# Programadapter.net
KiCad netlist of a schematic drawn in Altium Designer
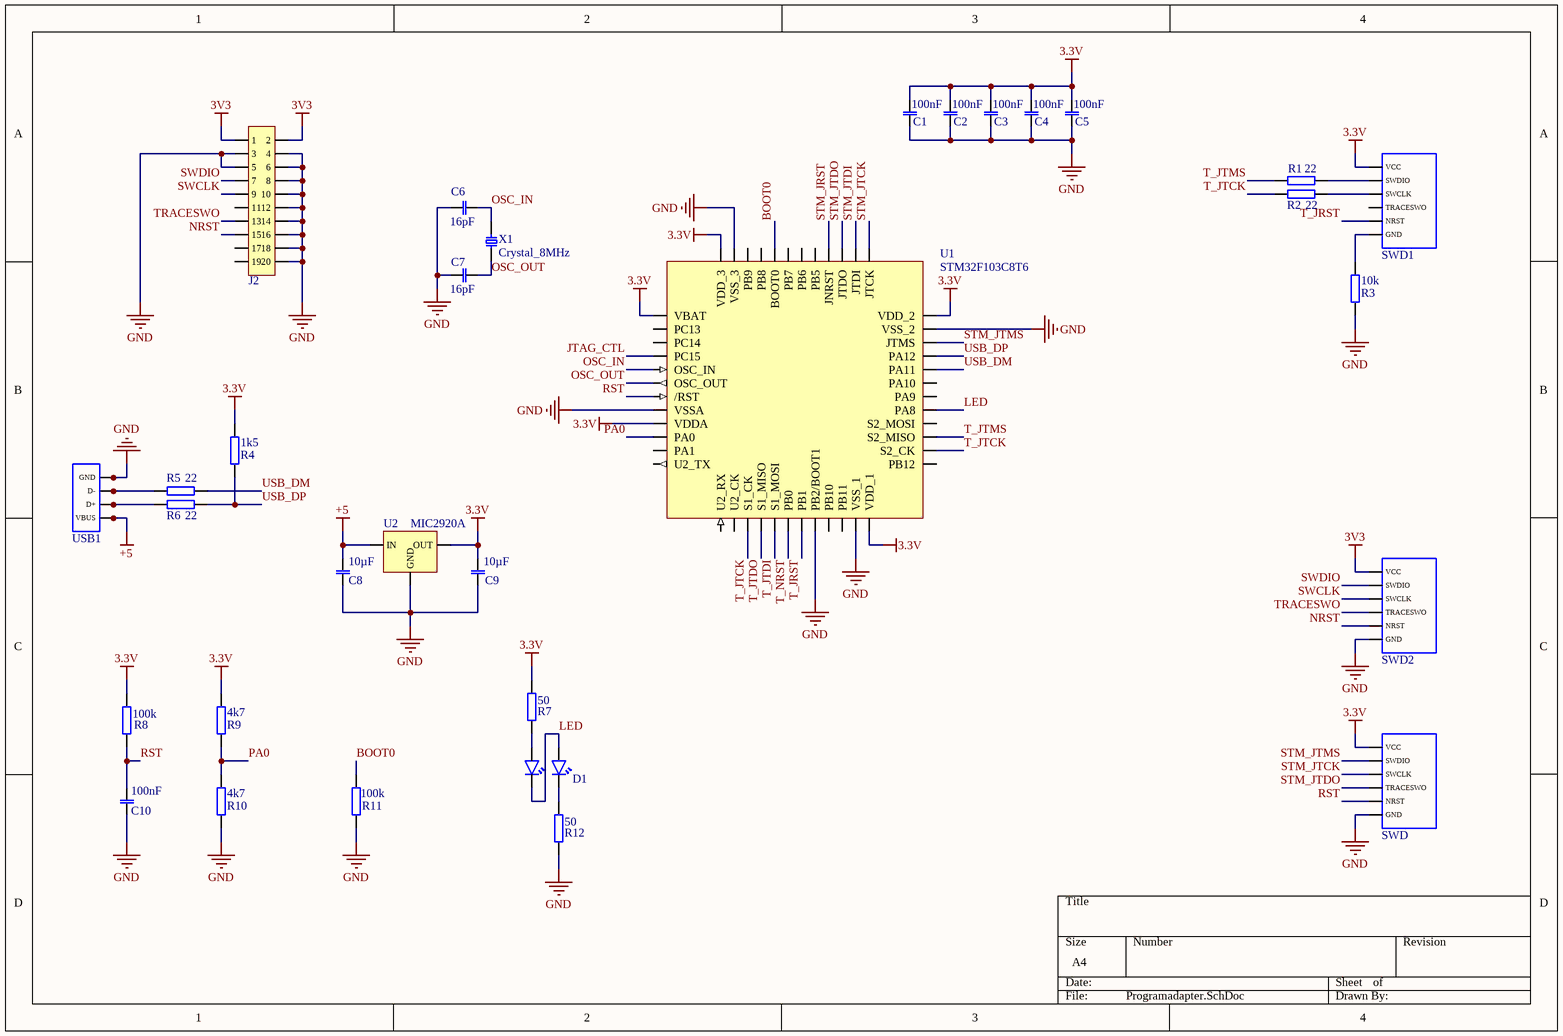
[diagram p0: Programadapter.SchDoc]

(export (version "E")
  (design (tool "Eeschema 10.0.6"))
  (components
    (comp (ref "C1")
      (value "Capacitor_0603")
      (footprint "C_0603_Chip2PinSM127P600-8N")
      (fields (field (name "CAPACITY") "100nF"))
      (libsource (lib "MiniWS") (part "Capacitor_0603"))
    )
    (comp (ref "C2")
      (value "Capacitor_0603")
      (footprint "C_0603_Chip2PinSM127P600-8N")
      (fields (field (name "CAPACITY") "100nF"))
      (libsource (lib "MiniWS") (part "Capacitor_0603"))
    )
    (comp (ref "C3")
      (value "Capacitor_0603")
      (footprint "C_0603_Chip2PinSM127P600-8N")
      (fields (field (name "CAPACITY") "100nF"))
      (libsource (lib "MiniWS") (part "Capacitor_0603"))
    )
    (comp (ref "C4")
      (value "Capacitor_0603")
      (footprint "C_0603_Chip2PinSM127P600-8N")
      (fields (field (name "CAPACITY") "100nF"))
      (libsource (lib "MiniWS") (part "Capacitor_0603"))
    )
    (comp (ref "C5")
      (value "Capacitor_0603")
      (footprint "C_0603_Chip2PinSM127P600-8N")
      (fields (field (name "CAPACITY") "100nF"))
      (libsource (lib "MiniWS") (part "Capacitor_0603"))
    )
    (comp (ref "C6")
      (value "Capacitor_0603")
      (footprint "C_0603_Chip2PinSM127P600-8N")
      (fields (field (name "CAPACITY") "16pF"))
      (libsource (lib "MiniWS") (part "Capacitor_0603"))
    )
    (comp (ref "C7")
      (value "Capacitor_0603")
      (footprint "C_0603_Chip2PinSM127P600-8N")
      (fields (field (name "CAPACITY") "16pF"))
      (libsource (lib "MiniWS") (part "Capacitor_0603"))
    )
    (comp (ref "C8")
      (value "Capacitor_0805")
      (footprint "10uF_0805_Chip2PinSM127P600-8N")
      (fields (field (name "CAPACITY") "10µF"))
      (libsource (lib "MiniWS") (part "Capacitor_0805"))
    )
    (comp (ref "C9")
      (value "Capacitor_0805")
      (footprint "10uF_0805_Chip2PinSM127P600-8N")
      (fields (field (name "CAPACITY") "10µF"))
      (libsource (lib "MiniWS") (part "Capacitor_0805"))
    )
    (comp (ref "C10")
      (value "Capacitor_0603")
      (footprint "C_0603_Chip2PinSM127P600-8N")
      (fields (field (name "CAPACITY") "100nF"))
      (libsource (lib "MiniWS") (part "Capacitor_0603"))
    )
    (comp (ref "D1")
      (value "LTST_LED_RED_GREEN")
      (footprint "LTST_LED_GREEN_RED")
      (libsource (lib "MiniWS") (part "LTST_LED_RED_GREEN"))
    )
    (comp (ref "J2")
      (value "JTAG_Header")
      (footprint "JTAG_Header")
      (libsource (lib "MiniWS") (part "JTAG_Header"))
    )
    (comp (ref "R1")
      (value "Resistor_0603")
      (footprint "R_0603_Chip2PinSM127P600-8N")
      (fields (field (name "RESISTANCE") "22"))
      (libsource (lib "MiniWS") (part "Resistor_0603"))
    )
    (comp (ref "R2")
      (value "Resistor_0603")
      (footprint "R_0603_Chip2PinSM127P600-8N")
      (fields (field (name "RESISTANCE") "22"))
      (libsource (lib "MiniWS") (part "Resistor_0603"))
    )
    (comp (ref "R3")
      (value "Resistor_0603")
      (footprint "R_0603_Chip2PinSM127P600-8N")
      (fields (field (name "RESISTANCE") "10k"))
      (libsource (lib "MiniWS") (part "Resistor_0603"))
    )
    (comp (ref "R4")
      (value "Resistor_0603")
      (footprint "R_0603_Chip2PinSM127P600-8N")
      (fields (field (name "RESISTANCE") "1k5"))
      (libsource (lib "MiniWS") (part "Resistor_0603"))
    )
    (comp (ref "R5")
      (value "Resistor_0603")
      (footprint "R_0603_Chip2PinSM127P600-8N")
      (fields (field (name "RESISTANCE") "22"))
      (libsource (lib "MiniWS") (part "Resistor_0603"))
    )
    (comp (ref "R6")
      (value "Resistor_0603")
      (footprint "R_0603_Chip2PinSM127P600-8N")
      (fields (field (name "RESISTANCE") "22"))
      (libsource (lib "MiniWS") (part "Resistor_0603"))
    )
    (comp (ref "R7")
      (value "Resistor_0603")
      (footprint "R_0603_Chip2PinSM127P600-8N")
      (fields (field (name "RESISTANCE") "50"))
      (libsource (lib "MiniWS") (part "Resistor_0603"))
    )
    (comp (ref "R8")
      (value "Resistor_0603")
      (footprint "R_0603_Chip2PinSM127P600-8N")
      (fields (field (name "RESISTANCE") "100k"))
      (libsource (lib "MiniWS") (part "Resistor_0603"))
    )
    (comp (ref "R9")
      (value "Resistor_0603")
      (footprint "R_0603_Chip2PinSM127P600-8N")
      (fields (field (name "RESISTANCE") "4k7"))
      (libsource (lib "MiniWS") (part "Resistor_0603"))
    )
    (comp (ref "R10")
      (value "Resistor_0603")
      (footprint "R_0603_Chip2PinSM127P600-8N")
      (fields (field (name "RESISTANCE") "4k7"))
      (libsource (lib "MiniWS") (part "Resistor_0603"))
    )
    (comp (ref "R11")
      (value "Resistor_0603")
      (footprint "R_0603_Chip2PinSM127P600-8N")
      (fields (field (name "RESISTANCE") "100k"))
      (libsource (lib "MiniWS") (part "Resistor_0603"))
    )
    (comp (ref "R12")
      (value "Resistor_0603")
      (footprint "R_0603_Chip2PinSM127P600-8N")
      (fields (field (name "RESISTANCE") "50"))
      (libsource (lib "MiniWS") (part "Resistor_0603"))
    )
    (comp (ref "SWD")
      (value "ProgrammingHeader")
      (footprint "ProgrammingHeader")
      (libsource (lib "MiniWS") (part "ProgrammingHeader"))
    )
    (comp (ref "SWD1")
      (value "ProgrammingHeader")
      (footprint "ProgrammingHeader")
      (libsource (lib "MiniWS") (part "ProgrammingHeader"))
    )
    (comp (ref "SWD2")
      (value "ProgrammingHeader")
      (footprint "ProgrammingHeader")
      (libsource (lib "MiniWS") (part "ProgrammingHeader"))
    )
    (comp (ref "U1")
      (value "STM32F103C8T6")
      (footprint "STM32F103CBT_LQFP48")
      (libsource (lib "MiniWS") (part "STM32F103C8T6"))
    )
    (comp (ref "U2")
      (value "MIC2920A")
      (footprint "MIC2920A_SOT230P710X170-4N")
      (libsource (lib "MiniWS") (part "MIC2920_3V3_VoltageReg"))
    )
    (comp (ref "USB1")
      (value "USB-C_simplified")
      (footprint "USB-C_receptacle")
      (description "USB Type C receptacle simplified with just data and supply pins")
      (libsource (lib "MiniWS") (part "USB-C_simplified"))
    )
    (comp (ref "X1")
      (value "Crystal_8MHz")
      (footprint "Crystal_8MHz")
      (description "8MHz Crystall SMD")
      (libsource (lib "MiniWS") (part "Crystal_8MHz"))
    )
  )
  (nets
    (net (code "1") (name "+5") (class "Default")
      (node (ref "C8") (pin "1") (pinfunction "1_1") (pintype "passive"))
      (node (ref "U2") (pin "1") (pinfunction "IN_1") (pintype "passive"))
      (node (ref "USB1") (pin "A4") (pinfunction "VBUS_A4") (pintype "passive"))
      (node (ref "USB1") (pin "A9") (pinfunction "VBUS_A9") (pintype "passive"))
      (node (ref "USB1") (pin "B4") (pinfunction "VBUS_B4") (pintype "passive"))
      (node (ref "USB1") (pin "B9") (pinfunction "VBUS_B9") (pintype "passive"))
    )
    (net (code "2") (name "/BOOT0") (class "Default")
      (node (ref "R11") (pin "2") (pinfunction "2_2") (pintype "passive"))
      (node (ref "U1") (pin "44") (pinfunction "BOOT0_44") (pintype "bidirectional"))
    )
    (net (code "3") (name "/JTAG_CTL") (class "Default")
      (node (ref "U1") (pin "4") (pinfunction "PC15_4") (pintype "bidirectional"))
    )
    (net (code "4") (name "/LED") (class "Default")
      (node (ref "D1") (pin "2") (pinfunction "2_2") (pintype "passive"))
      (node (ref "D1") (pin "4") (pinfunction "4_4") (pintype "passive"))
      (node (ref "U1") (pin "29") (pinfunction "PA8_29") (pintype "bidirectional"))
    )
    (net (code "5") (name "/NRST") (class "Default")
      (node (ref "J2") (pin "15") (pinfunction "15_15") (pintype "passive"))
      (node (ref "SWD2") (pin "5") (pinfunction "NRST_5") (pintype "passive"))
    )
    (net (code "6") (name "/OSC_IN") (class "Default")
      (node (ref "C6") (pin "2") (pinfunction "2_2") (pintype "passive"))
      (node (ref "U1") (pin "5") (pinfunction "OSC_IN_5") (pintype "input"))
      (node (ref "X1") (pin "2") (pinfunction "2_2") (pintype "passive"))
    )
    (net (code "7") (name "/OSC_OUT") (class "Default")
      (node (ref "C7") (pin "2") (pinfunction "2_2") (pintype "passive"))
      (node (ref "U1") (pin "6") (pinfunction "OSC_OUT_6") (pintype "output"))
      (node (ref "X1") (pin "1") (pinfunction "1_1") (pintype "passive"))
    )
    (net (code "8") (name "/PA0") (class "Default")
      (node (ref "R10") (pin "2") (pinfunction "2_2") (pintype "passive"))
      (node (ref "R9") (pin "1") (pinfunction "1_1") (pintype "passive"))
      (node (ref "U1") (pin "10") (pinfunction "PA0_10") (pintype "bidirectional"))
    )
    (net (code "9") (name "/RST") (class "Default")
      (node (ref "C10") (pin "1") (pinfunction "1_1") (pintype "passive"))
      (node (ref "R8") (pin "1") (pinfunction "1_1") (pintype "passive"))
      (node (ref "SWD") (pin "5") (pinfunction "NRST_5") (pintype "passive"))
      (node (ref "U1") (pin "7") (pinfunction "/RST_7") (pintype "input"))
    )
    (net (code "10") (name "/STM_JRST") (class "Default")
      (node (ref "U1") (pin "40") (pinfunction "JNRST_40") (pintype "bidirectional"))
    )
    (net (code "11") (name "/STM_JTCK") (class "Default")
      (node (ref "SWD") (pin "3") (pinfunction "SWCLK_3") (pintype "passive"))
      (node (ref "U1") (pin "37") (pinfunction "JTCK_37") (pintype "bidirectional"))
    )
    (net (code "12") (name "/STM_JTDI") (class "Default")
      (node (ref "U1") (pin "38") (pinfunction "JTDI_38") (pintype "bidirectional"))
    )
    (net (code "13") (name "/STM_JTDO") (class "Default")
      (node (ref "SWD") (pin "4") (pinfunction "TRACESWO_4") (pintype "passive"))
      (node (ref "U1") (pin "39") (pinfunction "JTDO_39") (pintype "bidirectional"))
    )
    (net (code "14") (name "/STM_JTMS") (class "Default")
      (node (ref "SWD") (pin "2") (pinfunction "SWDIO_2") (pintype "passive"))
      (node (ref "U1") (pin "34") (pinfunction "JTMS_34") (pintype "bidirectional"))
    )
    (net (code "15") (name "/SWCLK") (class "Default")
      (node (ref "J2") (pin "9") (pinfunction "9_9") (pintype "passive"))
      (node (ref "SWD2") (pin "3") (pinfunction "SWCLK_3") (pintype "passive"))
    )
    (net (code "16") (name "/SWDIO") (class "Default")
      (node (ref "J2") (pin "7") (pinfunction "7_7") (pintype "passive"))
      (node (ref "SWD2") (pin "2") (pinfunction "SWDIO_2") (pintype "passive"))
    )
    (net (code "17") (name "/TRACESWO") (class "Default")
      (node (ref "J2") (pin "13") (pinfunction "13_13") (pintype "passive"))
      (node (ref "SWD2") (pin "4") (pinfunction "TRACESWO_4") (pintype "passive"))
    )
    (net (code "18") (name "/T_JRST") (class "Default")
      (node (ref "SWD1") (pin "5") (pinfunction "NRST_5") (pintype "passive"))
      (node (ref "U1") (pin "19") (pinfunction "PB1_19") (pintype "passive"))
    )
    (net (code "19") (name "/T_JTCK") (class "Default")
      (node (ref "R2") (pin "1") (pinfunction "1_1") (pintype "passive"))
      (node (ref "U1") (pin "15") (pinfunction "S1_CK_15") (pintype "passive"))
      (node (ref "U1") (pin "26") (pinfunction "S2_CK_26") (pintype "passive"))
    )
    (net (code "20") (name "/T_JTDI") (class "Default")
      (node (ref "U1") (pin "17") (pinfunction "S1_MOSI_17") (pintype "passive"))
    )
    (net (code "21") (name "/T_JTDO") (class "Default")
      (node (ref "U1") (pin "16") (pinfunction "S1_MISO_16") (pintype "passive"))
    )
    (net (code "22") (name "/T_JTMS") (class "Default")
      (node (ref "R1") (pin "2") (pinfunction "2_2") (pintype "passive"))
      (node (ref "U1") (pin "27") (pinfunction "S2_MISO_27") (pintype "passive"))
    )
    (net (code "23") (name "/T_NRST") (class "Default")
      (node (ref "U1") (pin "18") (pinfunction "PB0_18") (pintype "passive"))
    )
    (net (code "24") (name "/USB_DM") (class "Default")
      (node (ref "R5") (pin "2") (pinfunction "2_2") (pintype "passive"))
      (node (ref "U1") (pin "32") (pinfunction "PA11_32") (pintype "bidirectional"))
    )
    (net (code "25") (name "/USB_DP") (class "Default")
      (node (ref "R4") (pin "1") (pinfunction "1_1") (pintype "passive"))
      (node (ref "R6") (pin "2") (pinfunction "2_2") (pintype "passive"))
      (node (ref "U1") (pin "33") (pinfunction "PA12_33") (pintype "bidirectional"))
    )
    (net (code "26") (name "3.3V") (class "Default")
      (node (ref "C1") (pin "1") (pinfunction "1_1") (pintype "passive"))
      (node (ref "C2") (pin "1") (pinfunction "1_1") (pintype "passive"))
      (node (ref "C3") (pin "1") (pinfunction "1_1") (pintype "passive"))
      (node (ref "C4") (pin "1") (pinfunction "1_1") (pintype "passive"))
      (node (ref "C5") (pin "1") (pinfunction "1_1") (pintype "passive"))
      (node (ref "C9") (pin "1") (pinfunction "1_1") (pintype "passive"))
      (node (ref "R4") (pin "2") (pinfunction "2_2") (pintype "passive"))
      (node (ref "R7") (pin "2") (pinfunction "2_2") (pintype "passive"))
      (node (ref "R8") (pin "2") (pinfunction "2_2") (pintype "passive"))
      (node (ref "R9") (pin "2") (pinfunction "2_2") (pintype "passive"))
      (node (ref "SWD") (pin "1") (pinfunction "VCC_1") (pintype "passive"))
      (node (ref "SWD1") (pin "1") (pinfunction "VCC_1") (pintype "passive"))
      (node (ref "U1") (pin "1") (pinfunction "VBAT_1") (pintype "passive"))
      (node (ref "U1") (pin "24") (pinfunction "VDD_1_24") (pintype "passive"))
      (node (ref "U1") (pin "36") (pinfunction "VDD_2_36") (pintype "passive"))
      (node (ref "U1") (pin "48") (pinfunction "VDD_3_48") (pintype "passive"))
      (node (ref "U1") (pin "9") (pinfunction "VDDA_9") (pintype "passive"))
      (node (ref "U2") (pin "3") (pinfunction "OUT_3") (pintype "passive"))
    )
    (net (code "27") (name "3V3") (class "Default")
      (node (ref "J2") (pin "1") (pinfunction "1_1") (pintype "passive"))
      (node (ref "J2") (pin "2") (pinfunction "2_2") (pintype "passive"))
      (node (ref "SWD2") (pin "1") (pinfunction "VCC_1") (pintype "passive"))
    )
    (net (code "28") (name "GND") (class "Default")
      (node (ref "C1") (pin "2") (pinfunction "2_2") (pintype "passive"))
      (node (ref "C10") (pin "2") (pinfunction "2_2") (pintype "passive"))
      (node (ref "C2") (pin "2") (pinfunction "2_2") (pintype "passive"))
      (node (ref "C3") (pin "2") (pinfunction "2_2") (pintype "passive"))
      (node (ref "C4") (pin "2") (pinfunction "2_2") (pintype "passive"))
      (node (ref "C5") (pin "2") (pinfunction "2_2") (pintype "passive"))
      (node (ref "C6") (pin "1") (pinfunction "1_1") (pintype "passive"))
      (node (ref "C7") (pin "1") (pinfunction "1_1") (pintype "passive"))
      (node (ref "C8") (pin "2") (pinfunction "2_2") (pintype "passive"))
      (node (ref "C9") (pin "2") (pinfunction "2_2") (pintype "passive"))
      (node (ref "J2") (pin "10") (pinfunction "10_10") (pintype "passive"))
      (node (ref "J2") (pin "12") (pinfunction "12_12") (pintype "passive"))
      (node (ref "J2") (pin "14") (pinfunction "14_14") (pintype "passive"))
      (node (ref "J2") (pin "16") (pinfunction "16_16") (pintype "passive"))
      (node (ref "J2") (pin "18") (pinfunction "18_18") (pintype "passive"))
      (node (ref "J2") (pin "20") (pinfunction "20_20") (pintype "passive"))
      (node (ref "J2") (pin "3") (pinfunction "3_3") (pintype "passive"))
      (node (ref "J2") (pin "4") (pinfunction "4_4") (pintype "passive"))
      (node (ref "J2") (pin "5") (pinfunction "5_5") (pintype "passive"))
      (node (ref "J2") (pin "6") (pinfunction "6_6") (pintype "passive"))
      (node (ref "J2") (pin "8") (pinfunction "8_8") (pintype "passive"))
      (node (ref "R10") (pin "1") (pinfunction "1_1") (pintype "passive"))
      (node (ref "R11") (pin "1") (pinfunction "1_1") (pintype "passive"))
      (node (ref "R12") (pin "1") (pinfunction "1_1") (pintype "passive"))
      (node (ref "R3") (pin "1") (pinfunction "1_1") (pintype "passive"))
      (node (ref "SWD") (pin "6") (pinfunction "GND_6") (pintype "passive"))
      (node (ref "SWD2") (pin "6") (pinfunction "GND_6") (pintype "passive"))
      (node (ref "U1") (pin "20") (pinfunction "PB2/BOOT1_20") (pintype "passive"))
      (node (ref "U1") (pin "23") (pinfunction "VSS_1_23") (pintype "passive"))
      (node (ref "U1") (pin "35") (pinfunction "VSS_2_35") (pintype "passive"))
      (node (ref "U1") (pin "47") (pinfunction "VSS_3_47") (pintype "passive"))
      (node (ref "U1") (pin "8") (pinfunction "VSSA_8") (pintype "passive"))
      (node (ref "U2") (pin "2") (pinfunction "GND_2") (pintype "passive"))
      (node (ref "USB1") (pin "A1") (pinfunction "GND_A1") (pintype "passive"))
      (node (ref "USB1") (pin "A12") (pinfunction "GND_A12") (pintype "passive"))
      (node (ref "USB1") (pin "B1") (pinfunction "GND_B1") (pintype "passive"))
      (node (ref "USB1") (pin "B12") (pinfunction "GND_B12") (pintype "passive"))
    )
    (net (code "29") (name "Net-(D1-Pad1)") (class "Default")
      (node (ref "D1") (pin "1") (pinfunction "1_1") (pintype "passive"))
      (node (ref "R7") (pin "1") (pinfunction "1_1") (pintype "passive"))
    )
    (net (code "30") (name "Net-(D1-Pad3)") (class "Default")
      (node (ref "D1") (pin "3") (pinfunction "3_3") (pintype "passive"))
      (node (ref "R12") (pin "2") (pinfunction "2_2") (pintype "passive"))
    )
    (net (code "31") (name "Net-(R5-Pad1)") (class "Default")
      (node (ref "R5") (pin "1") (pinfunction "1_1") (pintype "passive"))
      (node (ref "USB1") (pin "A7") (pinfunction "D-_A7") (pintype "passive"))
      (node (ref "USB1") (pin "B7") (pinfunction "D-_B7") (pintype "passive"))
    )
    (net (code "32") (name "Net-(R6-Pad1)") (class "Default")
      (node (ref "R6") (pin "1") (pinfunction "1_1") (pintype "passive"))
      (node (ref "USB1") (pin "A6") (pinfunction "D+_A6") (pintype "passive"))
      (node (ref "USB1") (pin "B6") (pinfunction "D+_B6") (pintype "passive"))
    )
    (net (code "33") (name "Net-(SWD1-GND)") (class "Default")
      (node (ref "R3") (pin "2") (pinfunction "2_2") (pintype "passive"))
      (node (ref "SWD1") (pin "6") (pinfunction "GND_6") (pintype "passive"))
    )
    (net (code "34") (name "Net-(SWD1-SWCLK)") (class "Default")
      (node (ref "R2") (pin "2") (pinfunction "2_2") (pintype "passive"))
      (node (ref "SWD1") (pin "3") (pinfunction "SWCLK_3") (pintype "passive"))
    )
    (net (code "35") (name "Net-(SWD1-SWDIO)") (class "Default")
      (node (ref "R1") (pin "1") (pinfunction "1_1") (pintype "passive"))
      (node (ref "SWD1") (pin "2") (pinfunction "SWDIO_2") (pintype "passive"))
    )
    (net (code "36") (name "unconnected-(J2-Pad11)") (class "Default")
      (node (ref "J2") (pin "11") (pinfunction "11_11") (pintype "passive"))
    )
    (net (code "37") (name "unconnected-(J2-Pad17)") (class "Default")
      (node (ref "J2") (pin "17") (pinfunction "17_17") (pintype "passive"))
    )
    (net (code "38") (name "unconnected-(J2-Pad19)") (class "Default")
      (node (ref "J2") (pin "19") (pinfunction "19_19") (pintype "passive"))
    )
    (net (code "39") (name "unconnected-(SWD1-TRACESWO-Pad4)") (class "Default")
      (node (ref "SWD1") (pin "4") (pinfunction "TRACESWO_4") (pintype "passive"))
    )
    (net (code "40") (name "unconnected-(U1-PA1-Pad11)") (class "Default")
      (node (ref "U1") (pin "11") (pinfunction "PA1_11") (pintype "bidirectional"))
    )
    (net (code "41") (name "unconnected-(U1-PA9-Pad30)") (class "Default")
      (node (ref "U1") (pin "30") (pinfunction "PA9_30") (pintype "bidirectional"))
    )
    (net (code "42") (name "unconnected-(U1-PA10-Pad31)") (class "Default")
      (node (ref "U1") (pin "31") (pinfunction "PA10_31") (pintype "bidirectional"))
    )
    (net (code "43") (name "unconnected-(U1-PB5-Pad41)") (class "Default")
      (node (ref "U1") (pin "41") (pinfunction "PB5_41") (pintype "bidirectional"))
    )
    (net (code "44") (name "unconnected-(U1-PB6-Pad42)") (class "Default")
      (node (ref "U1") (pin "42") (pinfunction "PB6_42") (pintype "bidirectional"))
    )
    (net (code "45") (name "unconnected-(U1-PB7-Pad43)") (class "Default")
      (node (ref "U1") (pin "43") (pinfunction "PB7_43") (pintype "bidirectional"))
    )
    (net (code "46") (name "unconnected-(U1-PB8-Pad45)") (class "Default")
      (node (ref "U1") (pin "45") (pinfunction "PB8_45") (pintype "bidirectional"))
    )
    (net (code "47") (name "unconnected-(U1-PB9-Pad46)") (class "Default")
      (node (ref "U1") (pin "46") (pinfunction "PB9_46") (pintype "bidirectional"))
    )
    (net (code "48") (name "unconnected-(U1-PB10-Pad21)") (class "Default")
      (node (ref "U1") (pin "21") (pinfunction "PB10_21") (pintype "bidirectional"))
    )
    (net (code "49") (name "unconnected-(U1-PB11-Pad22)") (class "Default")
      (node (ref "U1") (pin "22") (pinfunction "PB11_22") (pintype "passive"))
    )
    (net (code "50") (name "unconnected-(U1-PB12-Pad25)") (class "Default")
      (node (ref "U1") (pin "25") (pinfunction "PB12_25") (pintype "bidirectional"))
    )
    (net (code "51") (name "unconnected-(U1-PC13-Pad2)") (class "Default")
      (node (ref "U1") (pin "2") (pinfunction "PC13_2") (pintype "bidirectional"))
    )
    (net (code "52") (name "unconnected-(U1-PC14-Pad3)") (class "Default")
      (node (ref "U1") (pin "3") (pinfunction "PC14_3") (pintype "bidirectional"))
    )
    (net (code "53") (name "unconnected-(U1-S2_MOSI-Pad28)") (class "Default")
      (node (ref "U1") (pin "28") (pinfunction "S2_MOSI_28") (pintype "bidirectional"))
    )
    (net (code "54") (name "unconnected-(U1-U2_CK-Pad14)") (class "Default")
      (node (ref "U1") (pin "14") (pinfunction "U2_CK_14") (pintype "bidirectional"))
    )
    (net (code "55") (name "unconnected-(U1-U2_RX-Pad13)") (class "Default")
      (node (ref "U1") (pin "13") (pinfunction "U2_RX_13") (pintype "input"))
    )
    (net (code "56") (name "unconnected-(U1-U2_TX-Pad12)") (class "Default")
      (node (ref "U1") (pin "12") (pinfunction "U2_TX_12") (pintype "output"))
    )
  )
)
